# FM-Super-Regenerative-2.net
KiCad netlist of a schematic drawn in EAGLE
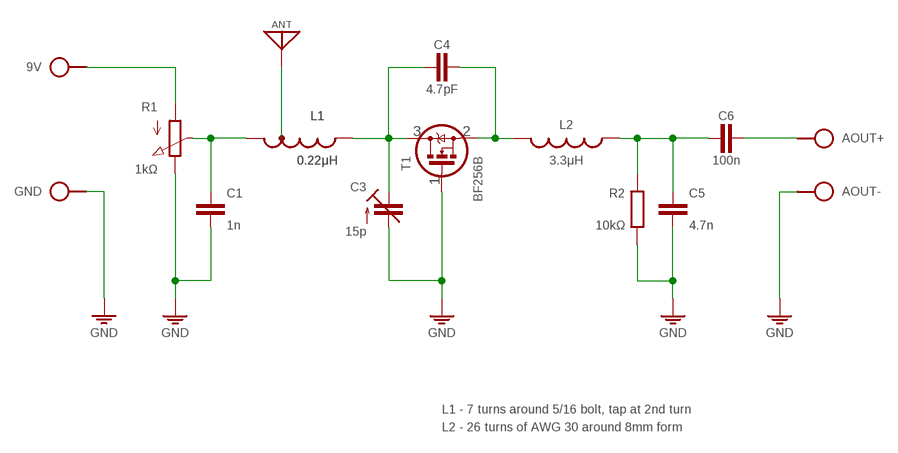
[diagram p0: schematic, sheet 1]

(export (version "E")
  (design (tool "Eeschema 10.0.6"))
  (components
    (comp (ref "9V")
      (value "SPAD")
      (footprint "eagle-import:SPAD")
      (libsource (lib "eagle-import") (part "SPAD"))
    )
    (comp (ref "ANT")
      (value "ANT")
      (footprint "eagle-import:SPAD")
      (libsource (lib "eagle-import") (part "ANT"))
    )
    (comp (ref "AOUT+")
      (value "SPAD")
      (footprint "eagle-import:SPAD")
      (libsource (lib "eagle-import") (part "SPAD"))
    )
    (comp (ref "AOUT-")
      (value "SPAD")
      (footprint "eagle-import:SPAD")
      (libsource (lib "eagle-import") (part "SPAD"))
    )
    (comp (ref "C1")
      (value "1n")
      (footprint "eagle-import:C050-025X060")
      (libsource (lib "eagle-import") (part "C025-025X060"))
    )
    (comp (ref "C3")
      (value "15p")
      (footprint "eagle-import:TRIM-2222-808")
      (libsource (lib "eagle-import") (part "C-TR-PH201272222-808-2PINB"))
    )
    (comp (ref "C4")
      (value "4.7pF")
      (footprint "eagle-import:C025-020X036")
      (libsource (lib "eagle-import") (part "C025-020X036"))
    )
    (comp (ref "C5")
      (value "4.7n")
      (footprint "eagle-import:C050-020X044")
      (libsource (lib "eagle-import") (part "C050-020X044"))
    )
    (comp (ref "C6")
      (value "100n")
      (footprint "eagle-import:C050-020X044")
      (libsource (lib "eagle-import") (part "C050-020X044"))
    )
    (comp (ref "GND")
      (value "SPAD")
      (footprint "eagle-import:SPAD")
      (libsource (lib "eagle-import") (part "SPAD"))
    )
    (comp (ref "L1")
      (value "0.22μH")
      (footprint "eagle-import:L-08_12-X-TAP1")
      (libsource (lib "eagle-import") (part "L-TAP1L-08/12-X-TAP1"))
    )
    (comp (ref "L2")
      (value "3.3μH")
      (footprint "eagle-import:L-BODY")
      (libsource (lib "eagle-import") (part "L-BODY"))
    )
    (comp (ref "R1")
      (value "1kΩ")
      (footprint "eagle-import:POT")
      (libsource (lib "eagle-import") (part "POT"))
    )
    (comp (ref "R2")
      (value "10kΩ")
      (footprint "eagle-import:0204_10")
      (libsource (lib "eagle-import") (part "R0204/10"))
    )
    (comp (ref "T1")
      (value "BF256B")
      (footprint "eagle-import:TO92")
      (libsource (lib "eagle-import") (part "BF256B"))
    )
  )
  (nets
    (net (code "1") (name "GND") (class "Default")
      (node (ref "AOUT-") (pin "1") (pinfunction "P$1_1") (pintype "bidirectional"))
      (node (ref "C1") (pin "2") (pinfunction "2_2") (pintype "passive"))
      (node (ref "C3") (pin "2") (pinfunction "A_2") (pintype "passive"))
      (node (ref "C5") (pin "2") (pinfunction "2_2") (pintype "passive"))
      (node (ref "GND") (pin "1") (pinfunction "P$1_1") (pintype "bidirectional"))
      (node (ref "R1") (pin "3") (pinfunction "E_3") (pintype "passive"))
      (node (ref "R2") (pin "1") (pinfunction "1_1") (pintype "passive"))
      (node (ref "T1") (pin "1") (pinfunction "G_1") (pintype "passive"))
    )
    (net (code "2") (name "Net-(9V-P$1)") (class "Default")
      (node (ref "9V") (pin "1") (pinfunction "P$1_1") (pintype "bidirectional"))
      (node (ref "R1") (pin "1") (pinfunction "A_1") (pintype "passive"))
    )
    (net (code "3") (name "Net-(AOUT+-P$1)") (class "Default")
      (node (ref "AOUT+") (pin "1") (pinfunction "P$1_1") (pintype "bidirectional"))
      (node (ref "C6") (pin "2") (pinfunction "2_2") (pintype "passive"))
    )
    (net (code "4") (name "Net-(C3-E)") (class "Default")
      (node (ref "C3") (pin "3") (pinfunction "E_3") (pintype "passive"))
      (node (ref "C4") (pin "1") (pinfunction "1_1") (pintype "passive"))
      (node (ref "L1") (pin "2") (pinfunction "2_2") (pintype "passive"))
      (node (ref "T1") (pin "3") (pinfunction "D_3") (pintype "passive"))
    )
    (net (code "5") (name "Net-(L1-T)") (class "Default")
      (node (ref "ANT") (pin "1") (pinfunction "1_1") (pintype "output"))
      (node (ref "L1") (pin "3") (pinfunction "T_3") (pintype "passive"))
    )
    (net (code "6") (name "Net-(L2-1)") (class "Default")
      (node (ref "C5") (pin "1") (pinfunction "1_1") (pintype "passive"))
      (node (ref "C6") (pin "1") (pinfunction "1_1") (pintype "passive"))
      (node (ref "L2") (pin "2") (pinfunction "1_2") (pintype "passive"))
      (node (ref "R2") (pin "2") (pinfunction "2_2") (pintype "passive"))
    )
    (net (code "7") (name "Net-(L2-2)") (class "Default")
      (node (ref "C4") (pin "2") (pinfunction "2_2") (pintype "passive"))
      (node (ref "L2") (pin "3") (pinfunction "2_3") (pintype "passive"))
      (node (ref "T1") (pin "2") (pinfunction "S_2") (pintype "passive"))
    )
    (net (code "8") (name "Net-(R1-S)") (class "Default")
      (node (ref "C1") (pin "1") (pinfunction "1_1") (pintype "passive"))
      (node (ref "L1") (pin "1") (pinfunction "1_1") (pintype "passive"))
      (node (ref "R1") (pin "2") (pinfunction "S_2") (pintype "passive"))
    )
  )
)
